# EEM_connector.net
KiCad netlist of a schematic drawn in Altium Designer
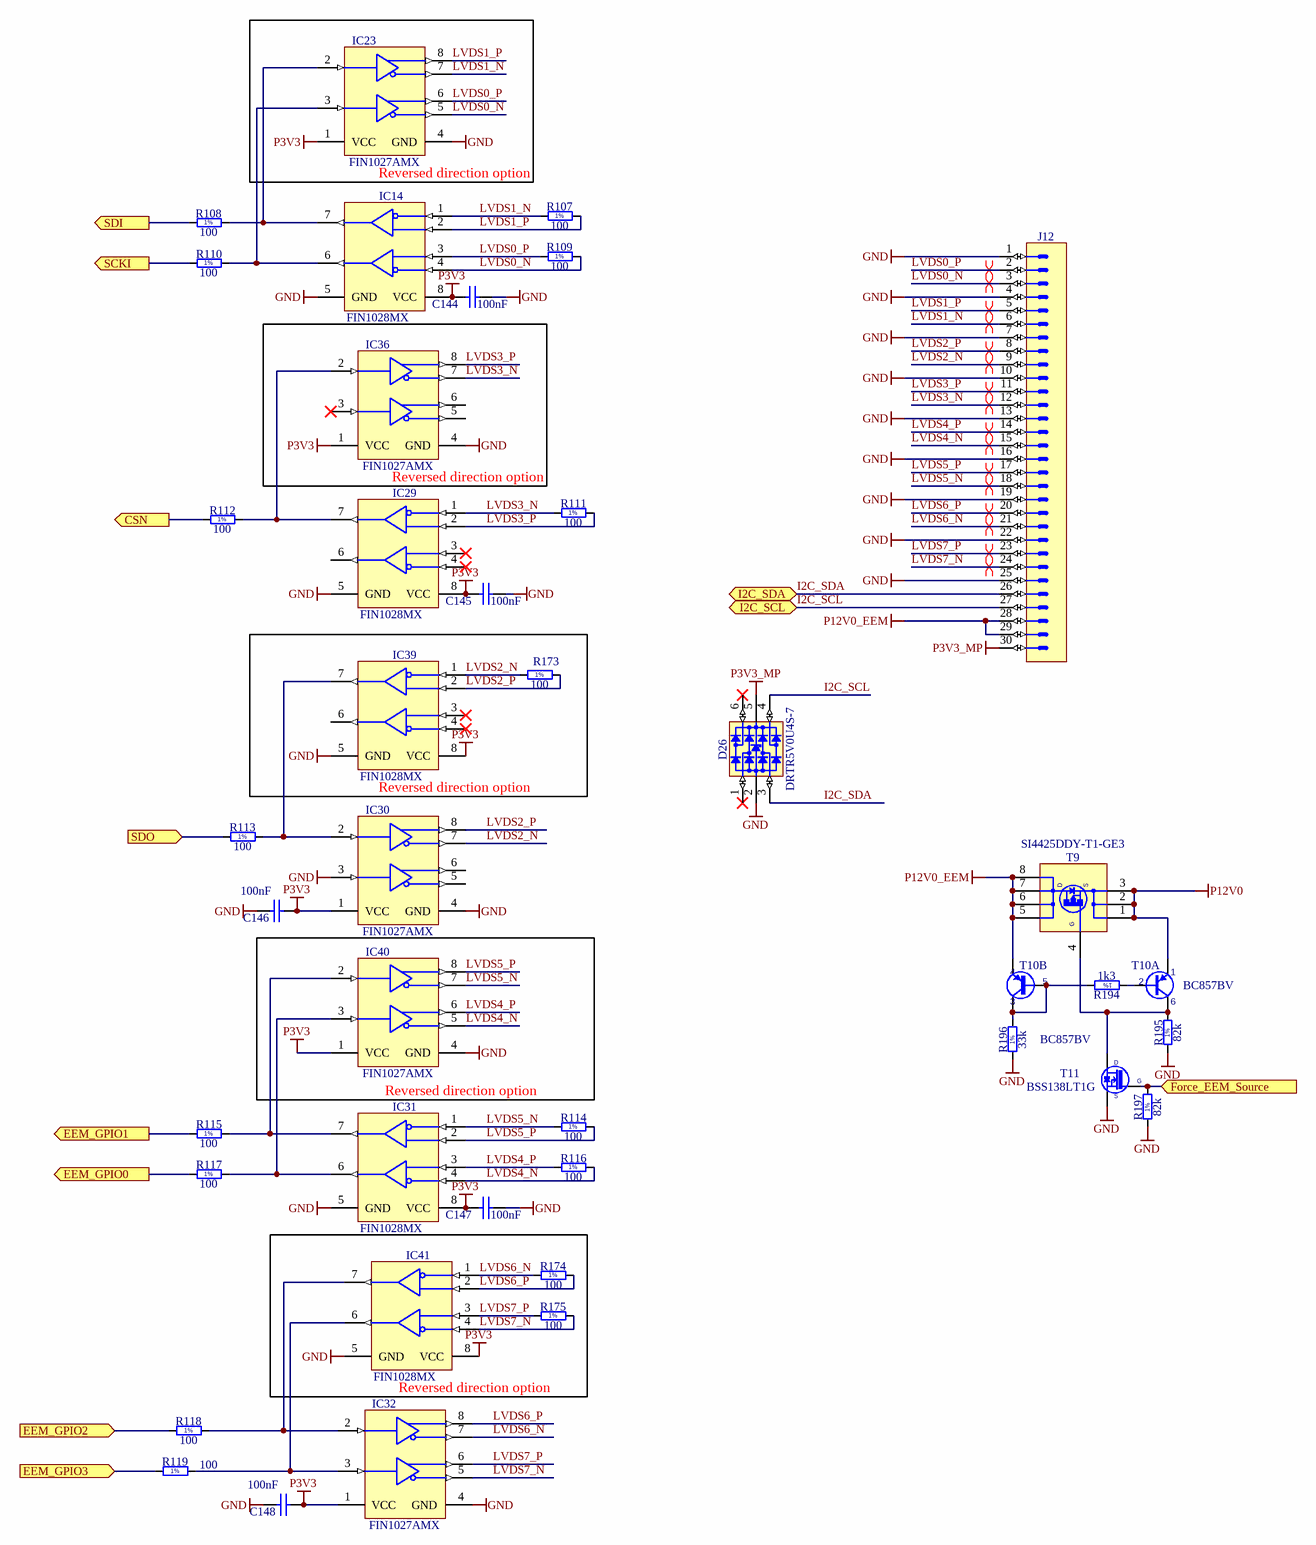
[diagram p0: EEM_connector.SchDoc]

(export (version "E")
  (design (tool "Eeschema 10.0.6"))
  (components
    (comp (ref "C144")
      (value "100nF")
      (footprint "CAPC1005X55N")
      (description "Non-polarised capacitor")
      (fields
        (field (name "PART NUMBER") "CC0402_100NF_16V_10%_X5R")
        (field (name "VOLTAGE") "16V")
        (field (name "AUTHOR") "CERN DEM JLC")
      )
      (libsource (lib "Capacitors") (part "Capacitor - non polarized"))
    )
    (comp (ref "C145")
      (value "100nF")
      (footprint "CAPC1005X55N")
      (description "Non-polarised capacitor")
      (fields
        (field (name "PART NUMBER") "CC0402_100NF_16V_10%_X5R")
        (field (name "VOLTAGE") "16V")
        (field (name "AUTHOR") "CERN DEM JLC")
      )
      (libsource (lib "Capacitors") (part "Capacitor - non polarized"))
    )
    (comp (ref "C146")
      (value "100nF")
      (footprint "CAPC1005X55N")
      (description "Non-polarised capacitor")
      (fields
        (field (name "PART NUMBER") "CC0402_100NF_16V_10%_X5R")
        (field (name "VOLTAGE") "16V")
        (field (name "AUTHOR") "CERN DEM JLC")
      )
      (libsource (lib "Capacitors") (part "Capacitor - non polarized"))
    )
    (comp (ref "C147")
      (value "100nF")
      (footprint "CAPC1005X55N")
      (description "Non-polarised capacitor")
      (fields
        (field (name "PART NUMBER") "CC0402_100NF_16V_10%_X5R")
        (field (name "VOLTAGE") "16V")
        (field (name "AUTHOR") "CERN DEM JLC")
      )
      (libsource (lib "Capacitors") (part "Capacitor - non polarized"))
    )
    (comp (ref "C148")
      (value "100nF")
      (footprint "CAPC1005X55N")
      (description "Non-polarised capacitor")
      (fields
        (field (name "PART NUMBER") "CC0402_100NF_16V_10%_X5R")
        (field (name "VOLTAGE") "16V")
        (field (name "AUTHOR") "CERN DEM JLC")
      )
      (libsource (lib "Capacitors") (part "Capacitor - non polarized"))
    )
    (comp (ref "D26")
      (value "DRTR5V0U4S-7")
      (footprint "SOT65P210X110-6N")
      (description "Integrated Quad Ultra-Low Capacitance ESD Protection")
      (fields (field (name "MANUFACTURER") "DIODES") (field (name "AUTHOR") "GK"))
      (libsource (lib "Diodes") (part "D_TVS_DRTR5V0U4S-7"))
    )
    (comp (ref "IC14")
      (value "FIN1028MX")
      (footprint "SOIC127P600X175-8N")
      (description "3.3V LVDS 2-Bit High-Speed Differential Reciever")
      (fields (field (name "MANUFACTURER") "ON Semiconductor") (field (name "AUTHOR") "GK"))
      (libsource (lib "LIBRARY_SCH") (part "IFC_FIN1028"))
    )
    (comp (ref "IC23")
      (value "FIN1027AMX")
      (footprint "SOIC127P600X175-8N")
      (description "3.3V LVDS, 2-Bit, High-Speed, Differential Driver")
      (fields (field (name "MANUFACTURER") "ON Semiconductor") (field (name "AUTHOR") "GK"))
      (libsource (lib "LIBRARY_SCH") (part "IFC_FIN1027A"))
    )
    (comp (ref "IC29")
      (value "FIN1028MX")
      (footprint "SOIC127P600X175-8N")
      (description "3.3V LVDS 2-Bit High-Speed Differential Reciever")
      (fields (field (name "MANUFACTURER") "ON Semiconductor") (field (name "AUTHOR") "GK"))
      (libsource (lib "LIBRARY_SCH") (part "IFC_FIN1028"))
    )
    (comp (ref "IC30")
      (value "FIN1027AMX")
      (footprint "SOIC127P600X175-8N")
      (description "3.3V LVDS, 2-Bit, High-Speed, Differential Driver")
      (fields (field (name "MANUFACTURER") "ON Semiconductor") (field (name "AUTHOR") "GK"))
      (libsource (lib "LIBRARY_SCH") (part "IFC_FIN1027A"))
    )
    (comp (ref "IC31")
      (value "FIN1028MX")
      (footprint "SOIC127P600X175-8N")
      (description "3.3V LVDS 2-Bit High-Speed Differential Reciever")
      (fields (field (name "MANUFACTURER") "ON Semiconductor") (field (name "AUTHOR") "GK"))
      (libsource (lib "LIBRARY_SCH") (part "IFC_FIN1028"))
    )
    (comp (ref "IC32")
      (value "FIN1027AMX")
      (footprint "SOIC127P600X175-8N")
      (description "3.3V LVDS, 2-Bit, High-Speed, Differential Driver")
      (fields (field (name "MANUFACTURER") "ON Semiconductor") (field (name "AUTHOR") "GK"))
      (libsource (lib "LIBRARY_SCH") (part "IFC_FIN1027A"))
    )
    (comp (ref "IC36")
      (value "FIN1027AMX")
      (footprint "SOIC127P600X175-8N")
      (description "3.3V LVDS, 2-Bit, High-Speed, Differential Driver")
      (fields (field (name "MANUFACTURER") "ON Semiconductor") (field (name "AUTHOR") "GK"))
      (libsource (lib "LIBRARY_SCH") (part "IFC_FIN1027A"))
    )
    (comp (ref "IC39")
      (value "FIN1028MX")
      (footprint "SOIC127P600X175-8N")
      (description "3.3V LVDS 2-Bit High-Speed Differential Reciever")
      (fields (field (name "MANUFACTURER") "ON Semiconductor") (field (name "AUTHOR") "GK"))
      (libsource (lib "LIBRARY_SCH") (part "IFC_FIN1028"))
    )
    (comp (ref "IC40")
      (value "FIN1027AMX")
      (footprint "SOIC127P600X175-8N")
      (description "3.3V LVDS, 2-Bit, High-Speed, Differential Driver")
      (fields (field (name "MANUFACTURER") "ON Semiconductor") (field (name "AUTHOR") "GK"))
      (libsource (lib "LIBRARY_SCH") (part "IFC_FIN1027A"))
    )
    (comp (ref "IC41")
      (value "FIN1028MX")
      (footprint "SOIC127P600X175-8N")
      (description "3.3V LVDS 2-Bit High-Speed Differential Reciever")
      (fields (field (name "MANUFACTURER") "ON Semiconductor") (field (name "AUTHOR") "GK"))
      (libsource (lib "LIBRARY_SCH") (part "IFC_FIN1028"))
    )
    (comp (ref "J12")
      (value "IDC")
      (footprint "3M_N2530-6002RB")
      (description "Connector 30 Male")
      (fields
        (field (name "PART NUMBER") "3M_N2530-6002RB")
        (field (name "MANUFACTURER") "3M")
        (field (name "AUTHOR") "CERN DEM JLC")
      )
      (libsource (lib "Connectors") (part "Connector 30 Male"))
    )
    (comp (ref "R107")
      (value "100")
      (footprint "RESC1005X40N")
      (description "Resistor - 1%")
      (fields
        (field (name "PART NUMBER") "R0402_100R_1%_0.0625W_100PPM")
        (field (name "POWER") "0.0625W")
        (field (name "AUTHOR") "CERN DEM JLC")
      )
      (libsource (lib "Resistors") (part "Resistor - 1%"))
    )
    (comp (ref "R108")
      (value "100")
      (footprint "RESC1005X40N")
      (description "Resistor - 1%")
      (fields
        (field (name "PART NUMBER") "R0402_100R_1%_0.0625W_100PPM")
        (field (name "POWER") "0.0625W")
        (field (name "AUTHOR") "CERN DEM JLC")
      )
      (libsource (lib "Resistors") (part "Resistor - 1%"))
    )
    (comp (ref "R109")
      (value "100")
      (footprint "RESC1005X40N")
      (description "Resistor - 1%")
      (fields
        (field (name "PART NUMBER") "R0402_100R_1%_0.0625W_100PPM")
        (field (name "POWER") "0.0625W")
        (field (name "AUTHOR") "CERN DEM JLC")
      )
      (libsource (lib "Resistors") (part "Resistor - 1%"))
    )
    (comp (ref "R110")
      (value "100")
      (footprint "RESC1005X40N")
      (description "Resistor - 1%")
      (fields
        (field (name "PART NUMBER") "R0402_100R_1%_0.0625W_100PPM")
        (field (name "POWER") "0.0625W")
        (field (name "AUTHOR") "CERN DEM JLC")
      )
      (libsource (lib "Resistors") (part "Resistor - 1%"))
    )
    (comp (ref "R111")
      (value "100")
      (footprint "RESC1005X40N")
      (description "Resistor - 1%")
      (fields
        (field (name "PART NUMBER") "R0402_100R_1%_0.0625W_100PPM")
        (field (name "POWER") "0.0625W")
        (field (name "AUTHOR") "CERN DEM JLC")
      )
      (libsource (lib "Resistors") (part "Resistor - 1%"))
    )
    (comp (ref "R112")
      (value "100")
      (footprint "RESC1005X40N")
      (description "Resistor - 1%")
      (fields
        (field (name "PART NUMBER") "R0402_100R_1%_0.0625W_100PPM")
        (field (name "POWER") "0.0625W")
        (field (name "AUTHOR") "CERN DEM JLC")
      )
      (libsource (lib "Resistors") (part "Resistor - 1%"))
    )
    (comp (ref "R113")
      (value "100")
      (footprint "RESC1005X40N")
      (description "Resistor - 1%")
      (fields
        (field (name "PART NUMBER") "R0402_100R_1%_0.0625W_100PPM")
        (field (name "POWER") "0.0625W")
        (field (name "AUTHOR") "CERN DEM JLC")
      )
      (libsource (lib "Resistors") (part "Resistor - 1%"))
    )
    (comp (ref "R114")
      (value "100")
      (footprint "RESC1005X40N")
      (description "Resistor - 1%")
      (fields
        (field (name "PART NUMBER") "R0402_100R_1%_0.0625W_100PPM")
        (field (name "POWER") "0.0625W")
        (field (name "AUTHOR") "CERN DEM JLC")
      )
      (libsource (lib "Resistors") (part "Resistor - 1%"))
    )
    (comp (ref "R115")
      (value "100")
      (footprint "RESC1005X40N")
      (description "Resistor - 1%")
      (fields
        (field (name "PART NUMBER") "R0402_100R_1%_0.0625W_100PPM")
        (field (name "POWER") "0.0625W")
        (field (name "AUTHOR") "CERN DEM JLC")
      )
      (libsource (lib "Resistors") (part "Resistor - 1%"))
    )
    (comp (ref "R116")
      (value "100")
      (footprint "RESC1005X40N")
      (description "Resistor - 1%")
      (fields
        (field (name "PART NUMBER") "R0402_100R_1%_0.0625W_100PPM")
        (field (name "POWER") "0.0625W")
        (field (name "AUTHOR") "CERN DEM JLC")
      )
      (libsource (lib "Resistors") (part "Resistor - 1%"))
    )
    (comp (ref "R117")
      (value "100")
      (footprint "RESC1005X40N")
      (description "Resistor - 1%")
      (fields
        (field (name "PART NUMBER") "R0402_100R_1%_0.0625W_100PPM")
        (field (name "POWER") "0.0625W")
        (field (name "AUTHOR") "CERN DEM JLC")
      )
      (libsource (lib "Resistors") (part "Resistor - 1%"))
    )
    (comp (ref "R118")
      (value "100")
      (footprint "RESC1005X40N")
      (description "Resistor - 1%")
      (fields
        (field (name "PART NUMBER") "R0402_100R_1%_0.0625W_100PPM")
        (field (name "POWER") "0.0625W")
        (field (name "AUTHOR") "CERN DEM JLC")
      )
      (libsource (lib "Resistors") (part "Resistor - 1%"))
    )
    (comp (ref "R119")
      (value "100")
      (footprint "RESC1005X40N")
      (description "Resistor - 1%")
      (fields
        (field (name "PART NUMBER") "R0402_100R_1%_0.0625W_100PPM")
        (field (name "POWER") "0.0625W")
        (field (name "AUTHOR") "CERN DEM JLC")
      )
      (libsource (lib "Resistors") (part "Resistor - 1%"))
    )
    (comp (ref "R173")
      (value "100")
      (footprint "RESC1005X40N")
      (description "Resistor - 1%")
      (fields
        (field (name "PART NUMBER") "R0402_100R_1%_0.0625W_100PPM")
        (field (name "POWER") "0.0625W")
        (field (name "AUTHOR") "CERN DEM JLC")
      )
      (libsource (lib "Resistors") (part "Resistor - 1%"))
    )
    (comp (ref "R174")
      (value "100")
      (footprint "RESC1005X40N")
      (description "Resistor - 1%")
      (fields
        (field (name "PART NUMBER") "R0402_100R_1%_0.0625W_100PPM")
        (field (name "POWER") "0.0625W")
        (field (name "AUTHOR") "CERN DEM JLC")
      )
      (libsource (lib "Resistors") (part "Resistor - 1%"))
    )
    (comp (ref "R175")
      (value "100")
      (footprint "RESC1005X40N")
      (description "Resistor - 1%")
      (fields
        (field (name "PART NUMBER") "R0402_100R_1%_0.0625W_100PPM")
        (field (name "POWER") "0.0625W")
        (field (name "AUTHOR") "CERN DEM JLC")
      )
      (libsource (lib "Resistors") (part "Resistor - 1%"))
    )
    (comp (ref "R194")
      (value "1k3")
      (footprint "RESC1608X55N")
      (description "Resistor - 1%")
      (fields
        (field (name "PART NUMBER") "R0603_1K3_1%_0.1W_100PPM")
        (field (name "POWER") "0.1W")
        (field (name "AUTHOR") "CERN DEM JLC")
      )
      (libsource (lib "Resistors") (part "Resistor - 1%"))
    )
    (comp (ref "R195")
      (value "82k")
      (footprint "RESC1608X55N")
      (description "Resistor - 1%")
      (fields
        (field (name "PART NUMBER") "R0603_82K_1%_0.1W_100PPM")
        (field (name "POWER") "0.1W")
        (field (name "AUTHOR") "CERN DEM JLC")
      )
      (libsource (lib "Resistors") (part "Resistor - 1%"))
    )
    (comp (ref "R196")
      (value "33k")
      (footprint "RESC1005X40N")
      (description "Resistor - 1%")
      (fields
        (field (name "PART NUMBER") "R0402_33K_1%_0.0625W_100PPM")
        (field (name "POWER") "0.0625W")
        (field (name "AUTHOR") "CERN DEM JLC")
      )
      (libsource (lib "Resistors") (part "Resistor - 1%"))
    )
    (comp (ref "R197")
      (value "82k")
      (footprint "RESC1608X55N")
      (description "Resistor - 1%")
      (fields
        (field (name "PART NUMBER") "R0603_82K_1%_0.1W_100PPM")
        (field (name "POWER") "0.1W")
        (field (name "AUTHOR") "CERN DEM JLC")
      )
      (libsource (lib "Resistors") (part "Resistor - 1%"))
    )
    (comp (ref "T9")
      (value "SI4425DDY-T1-GE3")
      (footprint "SOIC127P600X175-8N")
      (description "-30V -19.7A P-Channel MOSFET")
      (fields (field (name "MANUFACTURER") "VISHAY SILICONIX") (field (name "AUTHOR") "CERN DEM MR"))
      (libsource (lib "ICs And Semiconductors") (part "SI4425DDY"))
    )
    (comp (ref "T10")
      (value "BC857BV")
      (footprint "SOTFL50P160X60-6N")
      (description "45V, 100mA PNP General Purpose Double Transistor")
      (fields (field (name "MANUFACTURER") "NXP SEMICONDUCTORS") (field (name "AUTHOR") "CERN DEM JLC"))
      (libsource (lib "") (part "BC857BV_1"))
    )
    (comp (ref "T11")
      (value "BSS138LT1G")
      (footprint "SOT95P240X110-3N")
      (description "N-CHANNEL MOSFET WITH DIODE")
      (fields (field (name "MANUFACTURER") "ON SEMICONDUCTOR") (field (name "AUTHOR") "CERN DEM JLC"))
      (libsource (lib "ICs And Semiconductors") (part "N-MOSFET-D 1G 2S 3D"))
    )
  )
  (nets
    (net (code "1") (name "/CSN") (class "Default")
      (node (ref "R112") (pin "1") (pinfunction "1_1") (pintype "passive"))
    )
    (net (code "2") (name "/EEM_GPIO0") (class "Default")
      (node (ref "R117") (pin "1") (pinfunction "1_1") (pintype "passive"))
    )
    (net (code "3") (name "/EEM_GPIO1") (class "Default")
      (node (ref "R115") (pin "1") (pinfunction "1_1") (pintype "passive"))
    )
    (net (code "4") (name "/EEM_GPIO2") (class "Default")
      (node (ref "R118") (pin "1") (pinfunction "1_1") (pintype "passive"))
    )
    (net (code "5") (name "/EEM_GPIO3") (class "Default")
      (node (ref "R119") (pin "1") (pinfunction "1_1") (pintype "passive"))
    )
    (net (code "6") (name "/Force_EEM_Source") (class "Default")
      (node (ref "R197") (pin "2") (pinfunction "2_2") (pintype "passive"))
      (node (ref "T11") (pin "1") (pinfunction "G_1") (pintype "passive"))
    )
    (net (code "7") (name "/I2C_SCL") (class "Default")
      (node (ref "D26") (pin "4") (pinfunction "I/O3_4") (pintype "bidirectional"))
      (node (ref "J12") (pin "27") (pinfunction "27_27") (pintype "bidirectional"))
    )
    (net (code "8") (name "/I2C_SDA") (class "Default")
      (node (ref "D26") (pin "3") (pinfunction "I/O2_3") (pintype "bidirectional"))
      (node (ref "J12") (pin "26") (pinfunction "26_26") (pintype "bidirectional"))
    )
    (net (code "9") (name "/LVDS0_N") (class "Default")
      (node (ref "IC14") (pin "4") (pinfunction "RIN2-_4") (pintype "input"))
      (node (ref "IC23") (pin "5") (pinfunction "DOUT-_5") (pintype "output"))
      (node (ref "J12") (pin "3") (pinfunction "3_3") (pintype "bidirectional"))
      (node (ref "R109") (pin "2") (pinfunction "2_2") (pintype "passive"))
    )
    (net (code "10") (name "/LVDS0_P") (class "Default")
      (node (ref "IC14") (pin "3") (pinfunction "RIN2+_3") (pintype "input"))
      (node (ref "IC23") (pin "6") (pinfunction "DOUT+_6") (pintype "output"))
      (node (ref "J12") (pin "2") (pinfunction "2_2") (pintype "bidirectional"))
      (node (ref "R109") (pin "1") (pinfunction "1_1") (pintype "passive"))
    )
    (net (code "11") (name "/LVDS1_N") (class "Default")
      (node (ref "IC14") (pin "1") (pinfunction "RIN1-_1") (pintype "input"))
      (node (ref "IC23") (pin "7") (pinfunction "DOUT-_7") (pintype "output"))
      (node (ref "J12") (pin "6") (pinfunction "6_6") (pintype "bidirectional"))
      (node (ref "R107") (pin "1") (pinfunction "1_1") (pintype "passive"))
    )
    (net (code "12") (name "/LVDS1_P") (class "Default")
      (node (ref "IC14") (pin "2") (pinfunction "RIN1+_2") (pintype "input"))
      (node (ref "IC23") (pin "8") (pinfunction "DOUT+_8") (pintype "output"))
      (node (ref "J12") (pin "5") (pinfunction "5_5") (pintype "bidirectional"))
      (node (ref "R107") (pin "2") (pinfunction "2_2") (pintype "passive"))
    )
    (net (code "13") (name "/LVDS2_N") (class "Default")
      (node (ref "IC30") (pin "7") (pinfunction "DOUT-_7") (pintype "output"))
      (node (ref "IC39") (pin "1") (pinfunction "RIN1-_1") (pintype "input"))
      (node (ref "J12") (pin "9") (pinfunction "9_9") (pintype "bidirectional"))
      (node (ref "R173") (pin "1") (pinfunction "1_1") (pintype "passive"))
    )
    (net (code "14") (name "/LVDS2_P") (class "Default")
      (node (ref "IC30") (pin "8") (pinfunction "DOUT+_8") (pintype "output"))
      (node (ref "IC39") (pin "2") (pinfunction "RIN1+_2") (pintype "input"))
      (node (ref "J12") (pin "8") (pinfunction "8_8") (pintype "bidirectional"))
      (node (ref "R173") (pin "2") (pinfunction "2_2") (pintype "passive"))
    )
    (net (code "15") (name "/LVDS3_N") (class "Default")
      (node (ref "IC29") (pin "1") (pinfunction "RIN1-_1") (pintype "input"))
      (node (ref "IC36") (pin "7") (pinfunction "DOUT-_7") (pintype "output"))
      (node (ref "J12") (pin "12") (pinfunction "12_12") (pintype "bidirectional"))
      (node (ref "R111") (pin "1") (pinfunction "1_1") (pintype "passive"))
    )
    (net (code "16") (name "/LVDS3_P") (class "Default")
      (node (ref "IC29") (pin "2") (pinfunction "RIN1+_2") (pintype "input"))
      (node (ref "IC36") (pin "8") (pinfunction "DOUT+_8") (pintype "output"))
      (node (ref "J12") (pin "11") (pinfunction "11_11") (pintype "bidirectional"))
      (node (ref "R111") (pin "2") (pinfunction "2_2") (pintype "passive"))
    )
    (net (code "17") (name "/LVDS4_N") (class "Default")
      (node (ref "IC31") (pin "4") (pinfunction "RIN2-_4") (pintype "input"))
      (node (ref "IC40") (pin "5") (pinfunction "DOUT-_5") (pintype "output"))
      (node (ref "J12") (pin "15") (pinfunction "15_15") (pintype "bidirectional"))
      (node (ref "R116") (pin "2") (pinfunction "2_2") (pintype "passive"))
    )
    (net (code "18") (name "/LVDS4_P") (class "Default")
      (node (ref "IC31") (pin "3") (pinfunction "RIN2+_3") (pintype "input"))
      (node (ref "IC40") (pin "6") (pinfunction "DOUT+_6") (pintype "output"))
      (node (ref "J12") (pin "14") (pinfunction "14_14") (pintype "bidirectional"))
      (node (ref "R116") (pin "1") (pinfunction "1_1") (pintype "passive"))
    )
    (net (code "19") (name "/LVDS5_N") (class "Default")
      (node (ref "IC31") (pin "1") (pinfunction "RIN1-_1") (pintype "input"))
      (node (ref "IC40") (pin "7") (pinfunction "DOUT-_7") (pintype "output"))
      (node (ref "J12") (pin "18") (pinfunction "18_18") (pintype "bidirectional"))
      (node (ref "R114") (pin "1") (pinfunction "1_1") (pintype "passive"))
    )
    (net (code "20") (name "/LVDS5_P") (class "Default")
      (node (ref "IC31") (pin "2") (pinfunction "RIN1+_2") (pintype "input"))
      (node (ref "IC40") (pin "8") (pinfunction "DOUT+_8") (pintype "output"))
      (node (ref "J12") (pin "17") (pinfunction "17_17") (pintype "bidirectional"))
      (node (ref "R114") (pin "2") (pinfunction "2_2") (pintype "passive"))
    )
    (net (code "21") (name "/LVDS6_N") (class "Default")
      (node (ref "IC32") (pin "7") (pinfunction "DOUT-_7") (pintype "output"))
      (node (ref "IC41") (pin "1") (pinfunction "RIN1-_1") (pintype "input"))
      (node (ref "J12") (pin "21") (pinfunction "21_21") (pintype "bidirectional"))
      (node (ref "R174") (pin "1") (pinfunction "1_1") (pintype "passive"))
    )
    (net (code "22") (name "/LVDS6_P") (class "Default")
      (node (ref "IC32") (pin "8") (pinfunction "DOUT+_8") (pintype "output"))
      (node (ref "IC41") (pin "2") (pinfunction "RIN1+_2") (pintype "input"))
      (node (ref "J12") (pin "20") (pinfunction "20_20") (pintype "bidirectional"))
      (node (ref "R174") (pin "2") (pinfunction "2_2") (pintype "passive"))
    )
    (net (code "23") (name "/LVDS7_N") (class "Default")
      (node (ref "IC32") (pin "5") (pinfunction "DOUT-_5") (pintype "output"))
      (node (ref "IC41") (pin "4") (pinfunction "RIN2-_4") (pintype "input"))
      (node (ref "J12") (pin "24") (pinfunction "24_24") (pintype "bidirectional"))
      (node (ref "R175") (pin "2") (pinfunction "2_2") (pintype "passive"))
    )
    (net (code "24") (name "/LVDS7_P") (class "Default")
      (node (ref "IC32") (pin "6") (pinfunction "DOUT+_6") (pintype "output"))
      (node (ref "IC41") (pin "3") (pinfunction "RIN2+_3") (pintype "input"))
      (node (ref "J12") (pin "23") (pinfunction "23_23") (pintype "bidirectional"))
      (node (ref "R175") (pin "1") (pinfunction "1_1") (pintype "passive"))
    )
    (net (code "25") (name "/SCKI") (class "Default")
      (node (ref "R110") (pin "1") (pinfunction "1_1") (pintype "passive"))
    )
    (net (code "26") (name "/SDI") (class "Default")
      (node (ref "R108") (pin "1") (pinfunction "1_1") (pintype "passive"))
    )
    (net (code "27") (name "/SDO") (class "Default")
      (node (ref "R113") (pin "1") (pinfunction "1_1") (pintype "passive"))
    )
    (net (code "28") (name "GND") (class "Default")
      (node (ref "C144") (pin "1") (pinfunction "1_1") (pintype "passive"))
      (node (ref "C145") (pin "1") (pinfunction "1_1") (pintype "passive"))
      (node (ref "C146") (pin "1") (pinfunction "1_1") (pintype "passive"))
      (node (ref "C147") (pin "1") (pinfunction "1_1") (pintype "passive"))
      (node (ref "C148") (pin "1") (pinfunction "1_1") (pintype "passive"))
      (node (ref "D26") (pin "2") (pinfunction "GND_2") (pintype "power_in"))
      (node (ref "IC14") (pin "5") (pinfunction "GND_5") (pintype "power_in"))
      (node (ref "IC23") (pin "4") (pinfunction "GND_4") (pintype "power_in"))
      (node (ref "IC29") (pin "5") (pinfunction "GND_5") (pintype "power_in"))
      (node (ref "IC30") (pin "3") (pinfunction "DIN2RIN-_3") (pintype "input"))
      (node (ref "IC30") (pin "4") (pinfunction "GND_4") (pintype "power_in"))
      (node (ref "IC31") (pin "5") (pinfunction "GND_5") (pintype "power_in"))
      (node (ref "IC32") (pin "4") (pinfunction "GND_4") (pintype "power_in"))
      (node (ref "IC36") (pin "4") (pinfunction "GND_4") (pintype "power_in"))
      (node (ref "IC39") (pin "5") (pinfunction "GND_5") (pintype "power_in"))
      (node (ref "IC40") (pin "4") (pinfunction "GND_4") (pintype "power_in"))
      (node (ref "IC41") (pin "5") (pinfunction "GND_5") (pintype "power_in"))
      (node (ref "J12") (pin "1") (pinfunction "1_1") (pintype "bidirectional"))
      (node (ref "J12") (pin "10") (pinfunction "10_10") (pintype "bidirectional"))
      (node (ref "J12") (pin "13") (pinfunction "13_13") (pintype "bidirectional"))
      (node (ref "J12") (pin "16") (pinfunction "16_16") (pintype "bidirectional"))
      (node (ref "J12") (pin "19") (pinfunction "19_19") (pintype "bidirectional"))
      (node (ref "J12") (pin "22") (pinfunction "22_22") (pintype "bidirectional"))
      (node (ref "J12") (pin "25") (pinfunction "25_25") (pintype "bidirectional"))
      (node (ref "J12") (pin "4") (pinfunction "4_4") (pintype "bidirectional"))
      (node (ref "J12") (pin "7") (pinfunction "7_7") (pintype "bidirectional"))
      (node (ref "R195") (pin "1") (pinfunction "1_1") (pintype "passive"))
      (node (ref "R196") (pin "1") (pinfunction "1_1") (pintype "passive"))
      (node (ref "R197") (pin "1") (pinfunction "1_1") (pintype "passive"))
      (node (ref "T11") (pin "2") (pinfunction "S_2") (pintype "passive"))
    )
    (net (code "29") (name "Net-(IC14-ROUT1)") (class "Default")
      (node (ref "IC14") (pin "7") (pinfunction "ROUT1_7") (pintype "output"))
      (node (ref "IC23") (pin "2") (pinfunction "DIN1_2") (pintype "input"))
      (node (ref "R108") (pin "2") (pinfunction "2_2") (pintype "passive"))
    )
    (net (code "30") (name "Net-(IC14-ROUT2)") (class "Default")
      (node (ref "IC14") (pin "6") (pinfunction "ROUT2_6") (pintype "output"))
      (node (ref "IC23") (pin "3") (pinfunction "DIN2RIN-_3") (pintype "input"))
      (node (ref "R110") (pin "2") (pinfunction "2_2") (pintype "passive"))
    )
    (net (code "31") (name "Net-(IC29-ROUT1)") (class "Default")
      (node (ref "IC29") (pin "7") (pinfunction "ROUT1_7") (pintype "output"))
      (node (ref "IC36") (pin "2") (pinfunction "DIN1_2") (pintype "input"))
      (node (ref "R112") (pin "2") (pinfunction "2_2") (pintype "passive"))
    )
    (net (code "32") (name "Net-(IC30-DIN1)") (class "Default")
      (node (ref "IC30") (pin "2") (pinfunction "DIN1_2") (pintype "input"))
      (node (ref "IC39") (pin "7") (pinfunction "ROUT1_7") (pintype "output"))
      (node (ref "R113") (pin "2") (pinfunction "2_2") (pintype "passive"))
    )
    (net (code "33") (name "Net-(IC31-ROUT1)") (class "Default")
      (node (ref "IC31") (pin "7") (pinfunction "ROUT1_7") (pintype "output"))
      (node (ref "IC40") (pin "2") (pinfunction "DIN1_2") (pintype "input"))
      (node (ref "R115") (pin "2") (pinfunction "2_2") (pintype "passive"))
    )
    (net (code "34") (name "Net-(IC31-ROUT2)") (class "Default")
      (node (ref "IC31") (pin "6") (pinfunction "ROUT2_6") (pintype "output"))
      (node (ref "IC40") (pin "3") (pinfunction "DIN2RIN-_3") (pintype "input"))
      (node (ref "R117") (pin "2") (pinfunction "2_2") (pintype "passive"))
    )
    (net (code "35") (name "Net-(IC32-DIN1)") (class "Default")
      (node (ref "IC32") (pin "2") (pinfunction "DIN1_2") (pintype "input"))
      (node (ref "IC41") (pin "7") (pinfunction "ROUT1_7") (pintype "output"))
      (node (ref "R118") (pin "2") (pinfunction "2_2") (pintype "passive"))
    )
    (net (code "36") (name "Net-(IC32-DIN2RIN-)") (class "Default")
      (node (ref "IC32") (pin "3") (pinfunction "DIN2RIN-_3") (pintype "input"))
      (node (ref "IC41") (pin "6") (pinfunction "ROUT2_6") (pintype "output"))
      (node (ref "R119") (pin "2") (pinfunction "2_2") (pintype "passive"))
    )
    (net (code "37") (name "Net-(T10A-B)") (class "Default")
      (node (ref "R194") (pin "1") (pinfunction "1_1") (pintype "passive"))
      (node (ref "T10") (pin "2") (pinfunction "B_2") (pintype "passive"))
    )
    (net (code "38") (name "Net-(T10A-C)") (class "Default")
      (node (ref "R195") (pin "2") (pinfunction "2_2") (pintype "passive"))
      (node (ref "T10") (pin "6") (pinfunction "C_6") (pintype "passive"))
      (node (ref "T11") (pin "3") (pinfunction "D_3") (pintype "passive"))
      (node (ref "T9") (pin "4") (pinfunction "S_4") (pintype "passive"))
    )
    (net (code "39") (name "Net-(T10B-B)") (class "Default")
      (node (ref "R194") (pin "2") (pinfunction "2_2") (pintype "passive"))
      (node (ref "R196") (pin "2") (pinfunction "2_2") (pintype "passive"))
      (node (ref "T10") (pin "3") (pinfunction "C_3") (pintype "passive"))
      (node (ref "T10") (pin "5") (pinfunction "B_5") (pintype "passive"))
    )
    (net (code "40") (name "P3V3") (class "Default")
      (node (ref "C144") (pin "2") (pinfunction "2_2") (pintype "passive"))
      (node (ref "C145") (pin "2") (pinfunction "2_2") (pintype "passive"))
      (node (ref "C146") (pin "2") (pinfunction "2_2") (pintype "passive"))
      (node (ref "C147") (pin "2") (pinfunction "2_2") (pintype "passive"))
      (node (ref "C148") (pin "2") (pinfunction "2_2") (pintype "passive"))
      (node (ref "IC14") (pin "8") (pinfunction "VCC_8") (pintype "power_in"))
      (node (ref "IC23") (pin "1") (pinfunction "VCC_1") (pintype "power_in"))
      (node (ref "IC29") (pin "8") (pinfunction "VCC_8") (pintype "power_in"))
      (node (ref "IC30") (pin "1") (pinfunction "VCC_1") (pintype "power_in"))
      (node (ref "IC31") (pin "8") (pinfunction "VCC_8") (pintype "power_in"))
      (node (ref "IC32") (pin "1") (pinfunction "VCC_1") (pintype "power_in"))
      (node (ref "IC36") (pin "1") (pinfunction "VCC_1") (pintype "power_in"))
      (node (ref "IC39") (pin "8") (pinfunction "VCC_8") (pintype "power_in"))
      (node (ref "IC40") (pin "1") (pinfunction "VCC_1") (pintype "power_in"))
      (node (ref "IC41") (pin "8") (pinfunction "VCC_8") (pintype "power_in"))
    )
    (net (code "41") (name "P3V3_MP") (class "Default")
      (node (ref "D26") (pin "5") (pinfunction "VBUS_5") (pintype "power_in"))
      (node (ref "J12") (pin "30") (pinfunction "30_30") (pintype "bidirectional"))
    )
    (net (code "42") (name "P12V0") (class "Default")
      (node (ref "T10") (pin "1") (pinfunction "E_1") (pintype "passive"))
      (node (ref "T9") (pin "1") (pinfunction "S_1") (pintype "passive"))
      (node (ref "T9") (pin "2") (pinfunction "S_2") (pintype "passive"))
      (node (ref "T9") (pin "3") (pinfunction "S_3") (pintype "passive"))
    )
    (net (code "43") (name "P12V0_EEM") (class "Default")
      (node (ref "J12") (pin "28") (pinfunction "28_28") (pintype "bidirectional"))
      (node (ref "J12") (pin "29") (pinfunction "29_29") (pintype "bidirectional"))
      (node (ref "T10") (pin "4") (pinfunction "E_4") (pintype "passive"))
      (node (ref "T9") (pin "5") (pinfunction "D_5") (pintype "passive"))
      (node (ref "T9") (pin "6") (pinfunction "D_6") (pintype "passive"))
      (node (ref "T9") (pin "7") (pinfunction "D_7") (pintype "passive"))
      (node (ref "T9") (pin "8") (pinfunction "D_8") (pintype "passive"))
    )
    (net (code "44") (name "unconnected-(D26-I{slash}O1-Pad1)") (class "Default")
      (node (ref "D26") (pin "1") (pinfunction "I/O1_1") (pintype "bidirectional+no_connect"))
    )
    (net (code "45") (name "unconnected-(D26-I{slash}O4-Pad6)") (class "Default")
      (node (ref "D26") (pin "6") (pinfunction "I/O4_6") (pintype "bidirectional+no_connect"))
    )
    (net (code "46") (name "unconnected-(IC29-RIN2+-Pad3)") (class "Default")
      (node (ref "IC29") (pin "3") (pinfunction "RIN2+_3") (pintype "input+no_connect"))
    )
    (net (code "47") (name "unconnected-(IC29-RIN2--Pad4)") (class "Default")
      (node (ref "IC29") (pin "4") (pinfunction "RIN2-_4") (pintype "input+no_connect"))
    )
    (net (code "48") (name "unconnected-(IC29-ROUT2-Pad6)") (class "Default")
      (node (ref "IC29") (pin "6") (pinfunction "ROUT2_6") (pintype "output"))
    )
    (net (code "49") (name "unconnected-(IC30-DOUT+-Pad6)") (class "Default")
      (node (ref "IC30") (pin "6") (pinfunction "DOUT+_6") (pintype "output"))
    )
    (net (code "50") (name "unconnected-(IC30-DOUT--Pad5)") (class "Default")
      (node (ref "IC30") (pin "5") (pinfunction "DOUT-_5") (pintype "output"))
    )
    (net (code "51") (name "unconnected-(IC36-DIN2RIN--Pad3)") (class "Default")
      (node (ref "IC36") (pin "3") (pinfunction "DIN2RIN-_3") (pintype "input+no_connect"))
    )
    (net (code "52") (name "unconnected-(IC36-DOUT+-Pad6)") (class "Default")
      (node (ref "IC36") (pin "6") (pinfunction "DOUT+_6") (pintype "output"))
    )
    (net (code "53") (name "unconnected-(IC36-DOUT--Pad5)") (class "Default")
      (node (ref "IC36") (pin "5") (pinfunction "DOUT-_5") (pintype "output"))
    )
    (net (code "54") (name "unconnected-(IC39-RIN2+-Pad3)") (class "Default")
      (node (ref "IC39") (pin "3") (pinfunction "RIN2+_3") (pintype "input+no_connect"))
    )
    (net (code "55") (name "unconnected-(IC39-RIN2--Pad4)") (class "Default")
      (node (ref "IC39") (pin "4") (pinfunction "RIN2-_4") (pintype "input+no_connect"))
    )
    (net (code "56") (name "unconnected-(IC39-ROUT2-Pad6)") (class "Default")
      (node (ref "IC39") (pin "6") (pinfunction "ROUT2_6") (pintype "output"))
    )
  )
)
